# SAMD11_Feather_24QFN_WIP.net
KiCad netlist of a schematic drawn in EAGLE
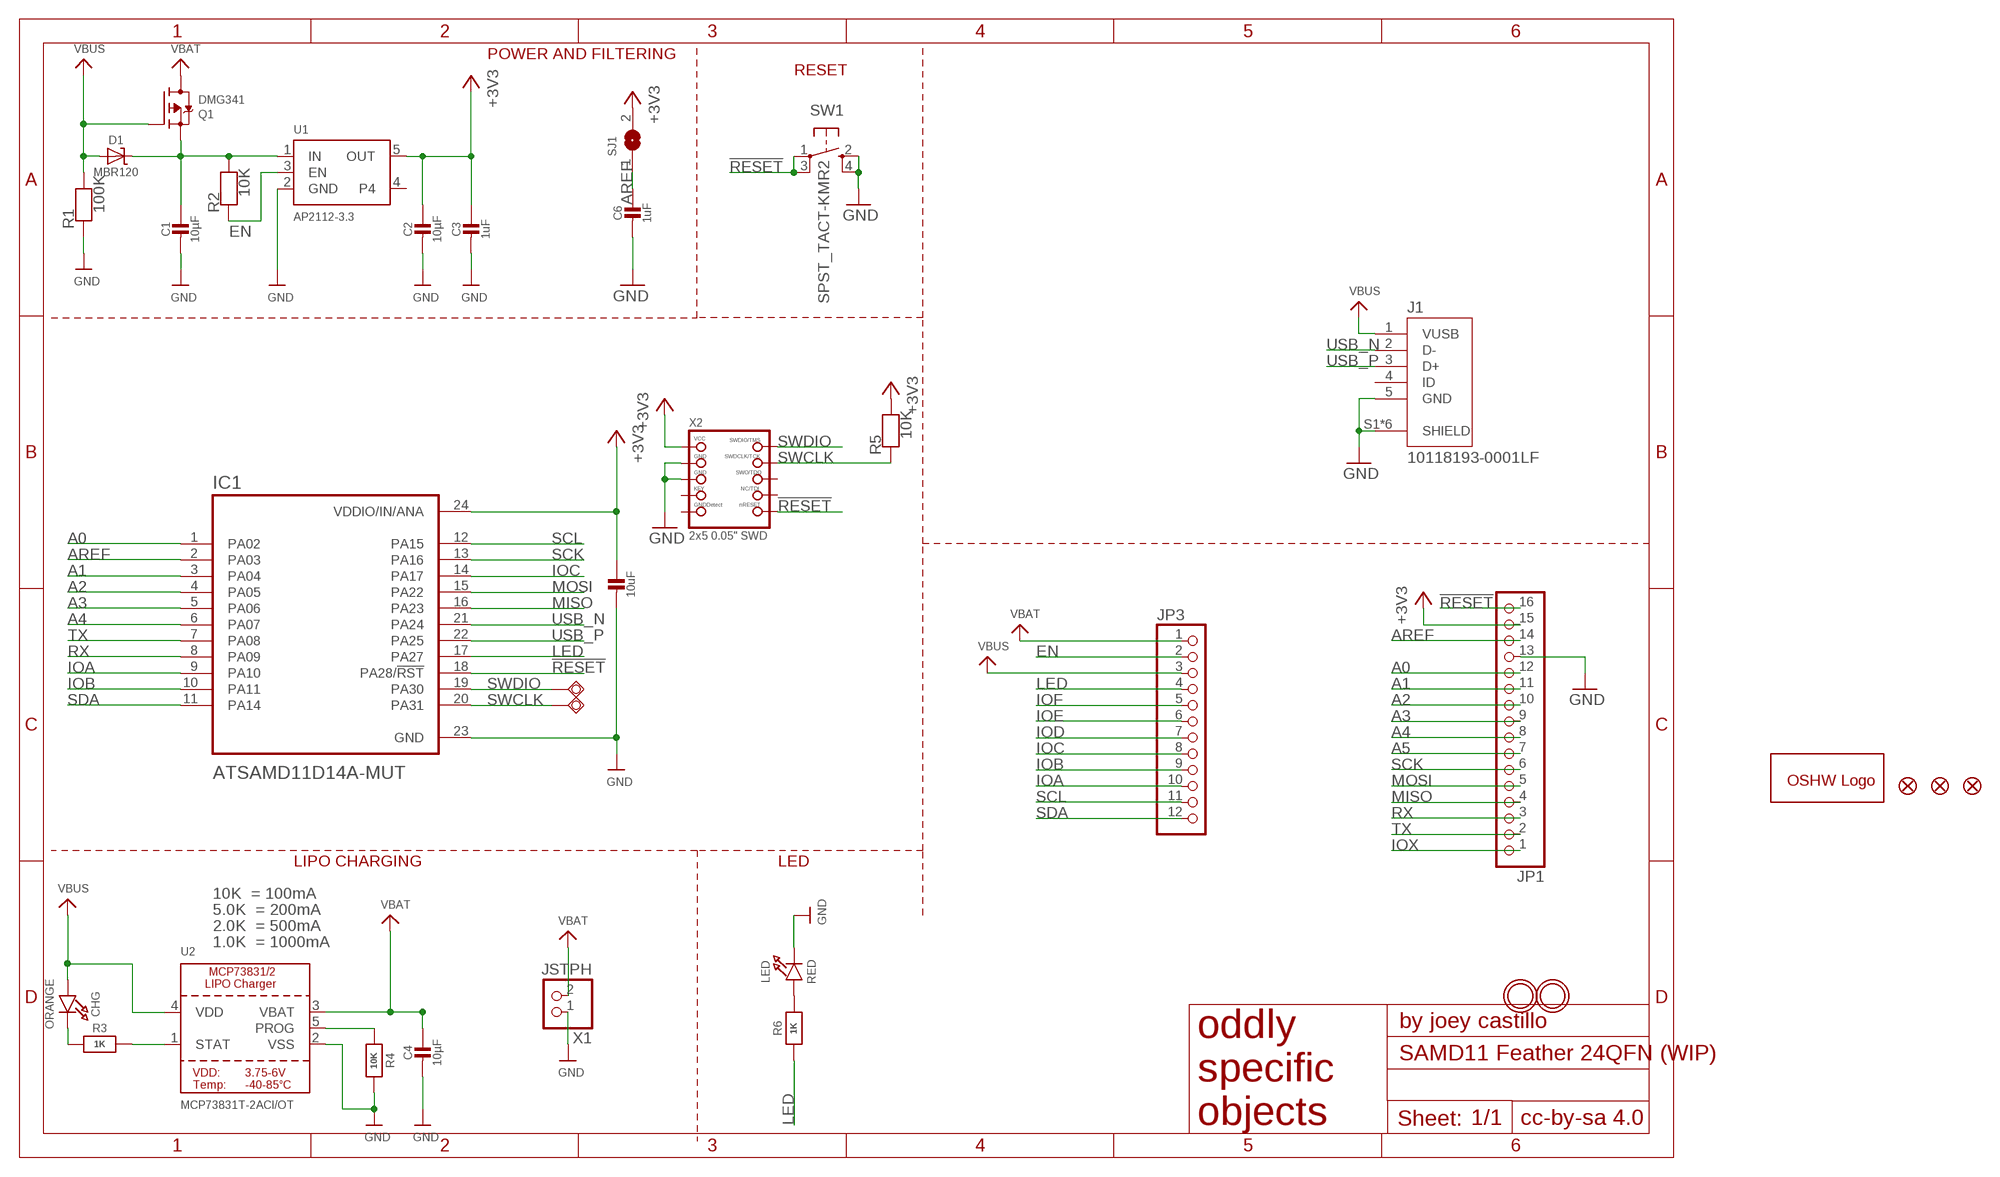
[diagram p0: schematic, sheet 1]

(export (version "E")
  (design (tool "Eeschema 10.0.6"))
  (components
    (comp (ref "C1")
      (value "10µF")
      (footprint "eagle-import:0805-NO")
      (libsource (lib "eagle-import") (part "CAP_CERAMIC0805-NOOUTLINE"))
    )
    (comp (ref "C2")
      (value "10µF")
      (footprint "eagle-import:0805-NO")
      (libsource (lib "eagle-import") (part "CAP_CERAMIC0805-NOOUTLINE"))
    )
    (comp (ref "C3")
      (value "1uF")
      (footprint "eagle-import:0805-NO")
      (libsource (lib "eagle-import") (part "CAP_CERAMIC0805-NOOUTLINE"))
    )
    (comp (ref "C4")
      (value "10µF")
      (footprint "eagle-import:0805-NO")
      (libsource (lib "eagle-import") (part "CAP_CERAMIC0805-NOOUTLINE"))
    )
    (comp (ref "C5")
      (value "10uF")
      (footprint "eagle-import:0805-NO")
      (libsource (lib "eagle-import") (part "CAP_CERAMIC0805-NOOUTLINE"))
    )
    (comp (ref "C6")
      (value "1uF")
      (footprint "eagle-import:0805-NO")
      (libsource (lib "eagle-import") (part "CAP_CERAMIC0805-NOOUTLINE"))
    )
    (comp (ref "CHG")
      (value "ORANGE")
      (footprint "eagle-import:CHIPLED_0805_NOOUTLINE")
      (libsource (lib "eagle-import") (part "LED0805_NOOUTLINE"))
    )
    (comp (ref "D1")
      (value "MBR120")
      (footprint "eagle-import:SOD-123")
      (libsource (lib "eagle-import") (part "DIODE-SCHOTTKYSOD-123"))
    )
    (comp (ref "FID1")
      (value "FIDUCIAL_1MM")
      (footprint "eagle-import:FIDUCIAL_1MM")
      (libsource (lib "eagle-import") (part "FIDUCIAL_1MM"))
    )
    (comp (ref "FID3")
      (value "FIDUCIAL_1MM")
      (footprint "eagle-import:FIDUCIAL_1MM")
      (libsource (lib "eagle-import") (part "FIDUCIAL_1MM"))
    )
    (comp (ref "FID4")
      (value "FIDUCIAL_1MM")
      (footprint "eagle-import:FIDUCIAL_1MM")
      (libsource (lib "eagle-import") (part "FIDUCIAL_1MM"))
    )
    (comp (ref "GOLD_ORB_SM1")
      (value "OSHWLOGOLOGO5MM")
      (footprint "eagle-import:OSHW_5MM")
      (libsource (lib "eagle-import") (part "OSHWLOGOLOGO5MM"))
    )
    (comp (ref "IC1")
      (value "ATSAMD11D14A-MUT")
      (footprint "eagle-import:QFN50P400X400X90-25N")
      (fields (field (name "MF") "Microchip"))
      (libsource (lib "eagle-import") (part "ATSAMD11D14A-MUT"))
    )
    (comp (ref "J1")
      (value "10118193-0001LF")
      (footprint "eagle-import:FCI_10118193-0001LF")
      (fields (field (name "DIGI-KEY_PART_NUMBER") "609-4616-1-ND") (field (name "MF") "Amphenol ICC"))
      (libsource (lib "eagle-import") (part "10118193-0001LF"))
    )
    (comp (ref "JP1")
      (value "HEADER-1X16_MIN")
      (footprint "eagle-import:1X16_ROUND_MIN")
      (libsource (lib "eagle-import") (part "HEADER-1X16_MIN"))
    )
    (comp (ref "JP3")
      (value "HEADER-1X12_MIN")
      (footprint "eagle-import:1X12_ROUND_MIN")
      (libsource (lib "eagle-import") (part "HEADER-1X12_MIN"))
    )
    (comp (ref "LED")
      (value "RED")
      (footprint "eagle-import:CHIPLED_0805_NOOUTLINE")
      (libsource (lib "eagle-import") (part "LED0805_NOOUTLINE"))
    )
    (comp (ref "Q1")
      (value "DMG341")
      (footprint "eagle-import:SOT23-R")
      (libsource (lib "eagle-import") (part "MOSFET-P"))
    )
    (comp (ref "R1")
      (value "100K")
      (footprint "eagle-import:0805-NO")
      (libsource (lib "eagle-import") (part "RESISTOR0805_NOOUTLINE"))
    )
    (comp (ref "R2")
      (value "10K")
      (footprint "eagle-import:0805-NO")
      (libsource (lib "eagle-import") (part "RESISTOR0805_NOOUTLINE"))
    )
    (comp (ref "R3")
      (value "1K")
      (footprint "eagle-import:0805-NO")
      (libsource (lib "eagle-import") (part "RESISTOR0805_NOOUTLINE"))
    )
    (comp (ref "R4")
      (value "10K")
      (footprint "eagle-import:0805-NO")
      (libsource (lib "eagle-import") (part "RESISTOR0805_NOOUTLINE"))
    )
    (comp (ref "R5")
      (value "10K")
      (footprint "eagle-import:0805-NO")
      (libsource (lib "eagle-import") (part "RESISTOR0805_NOOUTLINE"))
    )
    (comp (ref "R6")
      (value "1K")
      (footprint "eagle-import:0805-NO")
      (libsource (lib "eagle-import") (part "RESISTOR0805_NOOUTLINE"))
    )
    (comp (ref "SJ1")
      (value "SOLDERJUMPERCLOSED")
      (footprint "eagle-import:SOLDERJUMPER_CLOSEDWIRE")
      (libsource (lib "eagle-import") (part "SOLDERJUMPERCLOSED"))
    )
    (comp (ref "SW1")
      (value "SPST_TACT-KMR2")
      (footprint "eagle-import:KMR2")
      (libsource (lib "eagle-import") (part "SPST_TACT-KMR2"))
    )
    (comp (ref "SWCLK")
      (value "TPSQTP20R")
      (footprint "eagle-import:TP20R")
      (libsource (lib "eagle-import") (part "TPSQTP20R"))
    )
    (comp (ref "SWDIO")
      (value "TPSQTP20R")
      (footprint "eagle-import:TP20R")
      (libsource (lib "eagle-import") (part "TPSQTP20R"))
    )
    (comp (ref "U$31")
      (value "MOUNTINGHOLE2.5")
      (footprint "eagle-import:MOUNTINGHOLE_2.5_PLATED")
      (libsource (lib "eagle-import") (part "MOUNTINGHOLE2.5"))
    )
    (comp (ref "U$32")
      (value "MOUNTINGHOLE2.5")
      (footprint "eagle-import:MOUNTINGHOLE_2.5_PLATED")
      (libsource (lib "eagle-import") (part "MOUNTINGHOLE2.5"))
    )
    (comp (ref "U1")
      (value "AP2112-3.3")
      (footprint "eagle-import:SOT23-5")
      (libsource (lib "eagle-import") (part "VREG_SOT23-5"))
    )
    (comp (ref "U2")
      (value "MCP73831T-2ACI/OT")
      (footprint "eagle-import:SOT23-5")
      (libsource (lib "eagle-import") (part "MCP73831/2"))
    )
    (comp (ref "X1")
      (value "JSTPH")
      (footprint "eagle-import:JSTPH2")
      (libsource (lib "eagle-import") (part "CON_JST_PH_2PIN"))
    )
    (comp (ref "X2")
      (value "2x5 0.05\" SWD")
      (footprint "eagle-import:2X05_1.27MM_BOX_POSTS")
      (libsource (lib "eagle-import") (part "JTAG-CORTEXBOXPOSTS"))
    )
  )
  (nets
    (net (code "1") (name "+3V3") (class "Default")
      (node (ref "C2") (pin "1") (pinfunction "1_1") (pintype "passive"))
      (node (ref "C3") (pin "1") (pinfunction "1_1") (pintype "passive"))
      (node (ref "C5") (pin "1") (pinfunction "1_1") (pintype "passive"))
      (node (ref "IC1") (pin "24") (pinfunction "VDDIO/IN/ANA_24") (pintype "power_in"))
      (node (ref "JP1") (pin "15") (pinfunction "15_15") (pintype "passive"))
      (node (ref "R5") (pin "2") (pinfunction "2_2") (pintype "passive"))
      (node (ref "SJ1") (pin "2") (pinfunction "2_2") (pintype "passive"))
      (node (ref "U1") (pin "5") (pinfunction "OUT_5") (pintype "power_in"))
      (node (ref "X2") (pin "1") (pinfunction "VCC_1") (pintype "power_in"))
    )
    (net (code "2") (name "/A0") (class "Default")
      (node (ref "IC1") (pin "1") (pinfunction "PA02_1") (pintype "bidirectional"))
      (node (ref "JP1") (pin "12") (pinfunction "12_12") (pintype "passive"))
    )
    (net (code "3") (name "/A1") (class "Default")
      (node (ref "IC1") (pin "3") (pinfunction "PA04_3") (pintype "bidirectional"))
      (node (ref "JP1") (pin "11") (pinfunction "11_11") (pintype "passive"))
    )
    (net (code "4") (name "/A2") (class "Default")
      (node (ref "IC1") (pin "4") (pinfunction "PA05_4") (pintype "bidirectional"))
      (node (ref "JP1") (pin "10") (pinfunction "10_10") (pintype "passive"))
    )
    (net (code "5") (name "/A3") (class "Default")
      (node (ref "IC1") (pin "5") (pinfunction "PA06_5") (pintype "bidirectional"))
      (node (ref "JP1") (pin "9") (pinfunction "9_9") (pintype "passive"))
    )
    (net (code "6") (name "/A4") (class "Default")
      (node (ref "IC1") (pin "6") (pinfunction "PA07_6") (pintype "bidirectional"))
      (node (ref "JP1") (pin "8") (pinfunction "8_8") (pintype "passive"))
    )
    (net (code "7") (name "/A5") (class "Default")
      (node (ref "JP1") (pin "7") (pinfunction "7_7") (pintype "passive"))
    )
    (net (code "8") (name "/AREF") (class "Default")
      (node (ref "C6") (pin "1") (pinfunction "1_1") (pintype "passive"))
      (node (ref "IC1") (pin "2") (pinfunction "PA03_2") (pintype "bidirectional"))
      (node (ref "JP1") (pin "14") (pinfunction "14_14") (pintype "passive"))
      (node (ref "SJ1") (pin "1") (pinfunction "1_1") (pintype "passive"))
    )
    (net (code "9") (name "/EN") (class "Default")
      (node (ref "JP3") (pin "2") (pinfunction "2_2") (pintype "passive"))
      (node (ref "R2") (pin "1") (pinfunction "1_1") (pintype "passive"))
      (node (ref "U1") (pin "3") (pinfunction "EN_3") (pintype "input"))
    )
    (net (code "10") (name "/IOA") (class "Default")
      (node (ref "IC1") (pin "9") (pinfunction "PA10_9") (pintype "bidirectional"))
      (node (ref "JP3") (pin "10") (pinfunction "10_10") (pintype "passive"))
    )
    (net (code "11") (name "/IOB") (class "Default")
      (node (ref "IC1") (pin "10") (pinfunction "PA11_10") (pintype "bidirectional"))
      (node (ref "JP3") (pin "9") (pinfunction "9_9") (pintype "passive"))
    )
    (net (code "12") (name "/IOC") (class "Default")
      (node (ref "IC1") (pin "14") (pinfunction "PA17_14") (pintype "bidirectional"))
      (node (ref "JP3") (pin "8") (pinfunction "8_8") (pintype "passive"))
    )
    (net (code "13") (name "/IOD") (class "Default")
      (node (ref "JP3") (pin "7") (pinfunction "7_7") (pintype "passive"))
    )
    (net (code "14") (name "/IOE") (class "Default")
      (node (ref "JP3") (pin "6") (pinfunction "6_6") (pintype "passive"))
    )
    (net (code "15") (name "/IOF") (class "Default")
      (node (ref "JP3") (pin "5") (pinfunction "5_5") (pintype "passive"))
    )
    (net (code "16") (name "/IOX") (class "Default")
      (node (ref "JP1") (pin "1") (pinfunction "1_1") (pintype "passive"))
    )
    (net (code "17") (name "/LED") (class "Default")
      (node (ref "IC1") (pin "17") (pinfunction "PA27_17") (pintype "bidirectional"))
      (node (ref "JP3") (pin "4") (pinfunction "4_4") (pintype "passive"))
      (node (ref "R6") (pin "1") (pinfunction "1_1") (pintype "passive"))
    )
    (net (code "18") (name "/MISO") (class "Default")
      (node (ref "IC1") (pin "16") (pinfunction "PA23_16") (pintype "bidirectional"))
      (node (ref "JP1") (pin "4") (pinfunction "4_4") (pintype "passive"))
    )
    (net (code "19") (name "/MOSI") (class "Default")
      (node (ref "IC1") (pin "15") (pinfunction "PA22_15") (pintype "bidirectional"))
      (node (ref "JP1") (pin "5") (pinfunction "5_5") (pintype "passive"))
    )
    (net (code "20") (name "/RX") (class "Default")
      (node (ref "IC1") (pin "8") (pinfunction "PA09_8") (pintype "bidirectional"))
      (node (ref "JP1") (pin "3") (pinfunction "3_3") (pintype "passive"))
    )
    (net (code "21") (name "/SCK") (class "Default")
      (node (ref "IC1") (pin "13") (pinfunction "PA16_13") (pintype "bidirectional"))
      (node (ref "JP1") (pin "6") (pinfunction "6_6") (pintype "passive"))
    )
    (net (code "22") (name "/SCL") (class "Default")
      (node (ref "IC1") (pin "12") (pinfunction "PA15_12") (pintype "bidirectional"))
      (node (ref "JP3") (pin "11") (pinfunction "11_11") (pintype "passive"))
    )
    (net (code "23") (name "/SDA") (class "Default")
      (node (ref "IC1") (pin "11") (pinfunction "PA14_11") (pintype "bidirectional"))
      (node (ref "JP3") (pin "12") (pinfunction "12_12") (pintype "passive"))
    )
    (net (code "24") (name "/SWCLK") (class "Default")
      (node (ref "IC1") (pin "20") (pinfunction "PA31_20") (pintype "bidirectional"))
      (node (ref "R5") (pin "1") (pinfunction "1_1") (pintype "passive"))
      (node (ref "SWCLK") (pin "TP") (pinfunction "TP_TP") (pintype "input"))
      (node (ref "X2") (pin "4") (pinfunction "SWDCLK_4") (pintype "bidirectional"))
    )
    (net (code "25") (name "/SWDIO") (class "Default")
      (node (ref "IC1") (pin "19") (pinfunction "PA30_19") (pintype "bidirectional"))
      (node (ref "SWDIO") (pin "TP") (pinfunction "TP_TP") (pintype "input"))
      (node (ref "X2") (pin "2") (pinfunction "SWDIO_2") (pintype "bidirectional"))
    )
    (net (code "26") (name "/TX") (class "Default")
      (node (ref "IC1") (pin "7") (pinfunction "PA08_7") (pintype "bidirectional"))
      (node (ref "JP1") (pin "2") (pinfunction "2_2") (pintype "passive"))
    )
    (net (code "27") (name "/USB_N") (class "Default")
      (node (ref "IC1") (pin "21") (pinfunction "PA24_21") (pintype "bidirectional"))
      (node (ref "J1") (pin "2") (pinfunction "D-_2") (pintype "passive"))
    )
    (net (code "28") (name "/USB_P") (class "Default")
      (node (ref "IC1") (pin "22") (pinfunction "PA25_22") (pintype "bidirectional"))
      (node (ref "J1") (pin "3") (pinfunction "D+_3") (pintype "passive"))
    )
    (net (code "29") (name "/~{RESET}") (class "Default")
      (node (ref "IC1") (pin "18") (pinfunction "PA28/~{RST}_18") (pintype "bidirectional"))
      (node (ref "JP1") (pin "16") (pinfunction "16_16") (pintype "passive"))
      (node (ref "SW1") (pin "1") (pinfunction "P_1") (pintype "passive"))
      (node (ref "SW1") (pin "3") (pinfunction "P1_3") (pintype "passive"))
      (node (ref "X2") (pin "10") (pinfunction "NRESET_10") (pintype "bidirectional"))
    )
    (net (code "30") (name "GND") (class "Default")
      (node (ref "C1") (pin "2") (pinfunction "2_2") (pintype "passive"))
      (node (ref "C2") (pin "2") (pinfunction "2_2") (pintype "passive"))
      (node (ref "C3") (pin "2") (pinfunction "2_2") (pintype "passive"))
      (node (ref "C4") (pin "2") (pinfunction "2_2") (pintype "passive"))
      (node (ref "C5") (pin "2") (pinfunction "2_2") (pintype "passive"))
      (node (ref "C6") (pin "2") (pinfunction "2_2") (pintype "passive"))
      (node (ref "IC1") (pin "23") (pinfunction "GND_23") (pintype "power_in"))
      (node (ref "J1") (pin "5") (pinfunction "GND_5") (pintype "passive"))
      (node (ref "J1") (pin "S1") (pinfunction "SHIELD_S1") (pintype "passive"))
      (node (ref "J1") (pin "S2") (pinfunction "SHIELD_S2") (pintype "passive"))
      (node (ref "J1") (pin "S3") (pinfunction "SHIELD_S3") (pintype "passive"))
      (node (ref "J1") (pin "S4") (pinfunction "SHIELD_S4") (pintype "passive"))
      (node (ref "J1") (pin "S5") (pinfunction "SHIELD_S5") (pintype "passive"))
      (node (ref "J1") (pin "S6") (pinfunction "SHIELD_S6") (pintype "passive"))
      (node (ref "JP1") (pin "13") (pinfunction "13_13") (pintype "passive"))
      (node (ref "LED") (pin "C") (pinfunction "C_C") (pintype "passive"))
      (node (ref "R1") (pin "1") (pinfunction "1_1") (pintype "passive"))
      (node (ref "R4") (pin "2") (pinfunction "2_2") (pintype "passive"))
      (node (ref "SW1") (pin "2") (pinfunction "S_2") (pintype "passive"))
      (node (ref "SW1") (pin "4") (pinfunction "S1_4") (pintype "passive"))
      (node (ref "U1") (pin "2") (pinfunction "GND_2") (pintype "power_in"))
      (node (ref "U2") (pin "2") (pinfunction "VSS_2") (pintype "power_in"))
      (node (ref "X1") (pin "1") (pinfunction "1_1") (pintype "passive"))
      (node (ref "X2") (pin "3") (pinfunction "GND_3") (pintype "power_in"))
      (node (ref "X2") (pin "5") (pinfunction "GND_5") (pintype "power_in"))
    )
    (net (code "31") (name "Net-(CHG-PadC)") (class "Default")
      (node (ref "CHG") (pin "C") (pinfunction "C_C") (pintype "passive"))
      (node (ref "R3") (pin "1") (pinfunction "1_1") (pintype "passive"))
    )
    (net (code "32") (name "Net-(LED-PadA)") (class "Default")
      (node (ref "LED") (pin "A") (pinfunction "A_A") (pintype "passive"))
      (node (ref "R6") (pin "2") (pinfunction "2_2") (pintype "passive"))
    )
    (net (code "33") (name "Net-(Q1-S)") (class "Default")
      (node (ref "C1") (pin "1") (pinfunction "1_1") (pintype "passive"))
      (node (ref "D1") (pin "C") (pinfunction "C_C") (pintype "passive"))
      (node (ref "Q1") (pin "2") (pinfunction "S_2") (pintype "passive"))
      (node (ref "R2") (pin "2") (pinfunction "2_2") (pintype "passive"))
      (node (ref "U1") (pin "1") (pinfunction "IN_1") (pintype "power_in"))
    )
    (net (code "34") (name "Net-(U2-PROG)") (class "Default")
      (node (ref "R4") (pin "1") (pinfunction "1_1") (pintype "passive"))
      (node (ref "U2") (pin "5") (pinfunction "PROG_5") (pintype "input"))
    )
    (net (code "35") (name "Net-(U2-STAT)") (class "Default")
      (node (ref "R3") (pin "2") (pinfunction "2_2") (pintype "passive"))
      (node (ref "U2") (pin "1") (pinfunction "STAT_1") (pintype "output"))
    )
    (net (code "36") (name "VBAT") (class "Default")
      (node (ref "C4") (pin "1") (pinfunction "1_1") (pintype "passive"))
      (node (ref "JP3") (pin "1") (pinfunction "1_1") (pintype "passive"))
      (node (ref "Q1") (pin "3") (pinfunction "D_3") (pintype "passive"))
      (node (ref "U2") (pin "3") (pinfunction "VBAT_3") (pintype "power_in"))
      (node (ref "X1") (pin "2") (pinfunction "2_2") (pintype "passive"))
    )
    (net (code "37") (name "VBUS") (class "Default")
      (node (ref "CHG") (pin "A") (pinfunction "A_A") (pintype "passive"))
      (node (ref "D1") (pin "A") (pinfunction "A_A") (pintype "passive"))
      (node (ref "J1") (pin "1") (pinfunction "VUSB_1") (pintype "passive"))
      (node (ref "JP3") (pin "3") (pinfunction "3_3") (pintype "passive"))
      (node (ref "Q1") (pin "1") (pinfunction "G_1") (pintype "passive"))
      (node (ref "R1") (pin "2") (pinfunction "2_2") (pintype "passive"))
      (node (ref "U2") (pin "4") (pinfunction "VDD_4") (pintype "power_in"))
    )
    (net (code "38") (name "unconnected-(J1-ID-Pad4)") (class "Default")
      (node (ref "J1") (pin "4") (pinfunction "ID_4") (pintype "passive"))
    )
    (net (code "39") (name "unconnected-(U1-P4-Pad4)") (class "Default")
      (node (ref "U1") (pin "4") (pinfunction "P4_4") (pintype "bidirectional"))
    )
    (net (code "40") (name "unconnected-(X2-GNDDETECT-Pad9)") (class "Default")
      (node (ref "X2") (pin "9") (pinfunction "GNDDETECT_9") (pintype "bidirectional"))
    )
    (net (code "41") (name "unconnected-(X2-KEY-Pad7)") (class "Default")
      (node (ref "X2") (pin "7") (pinfunction "KEY_7") (pintype "bidirectional"))
    )
    (net (code "42") (name "unconnected-(X2-SWO-Pad6)") (class "Default")
      (node (ref "X2") (pin "6") (pinfunction "SWO_6") (pintype "bidirectional"))
    )
    (net (code "43") (name "unconnected-(X2-TDI-Pad8)") (class "Default")
      (node (ref "X2") (pin "8") (pinfunction "TDI_8") (pintype "bidirectional"))
    )
  )
)
